# RF_DAC.net
KiCad netlist of a schematic drawn in Altium Designer
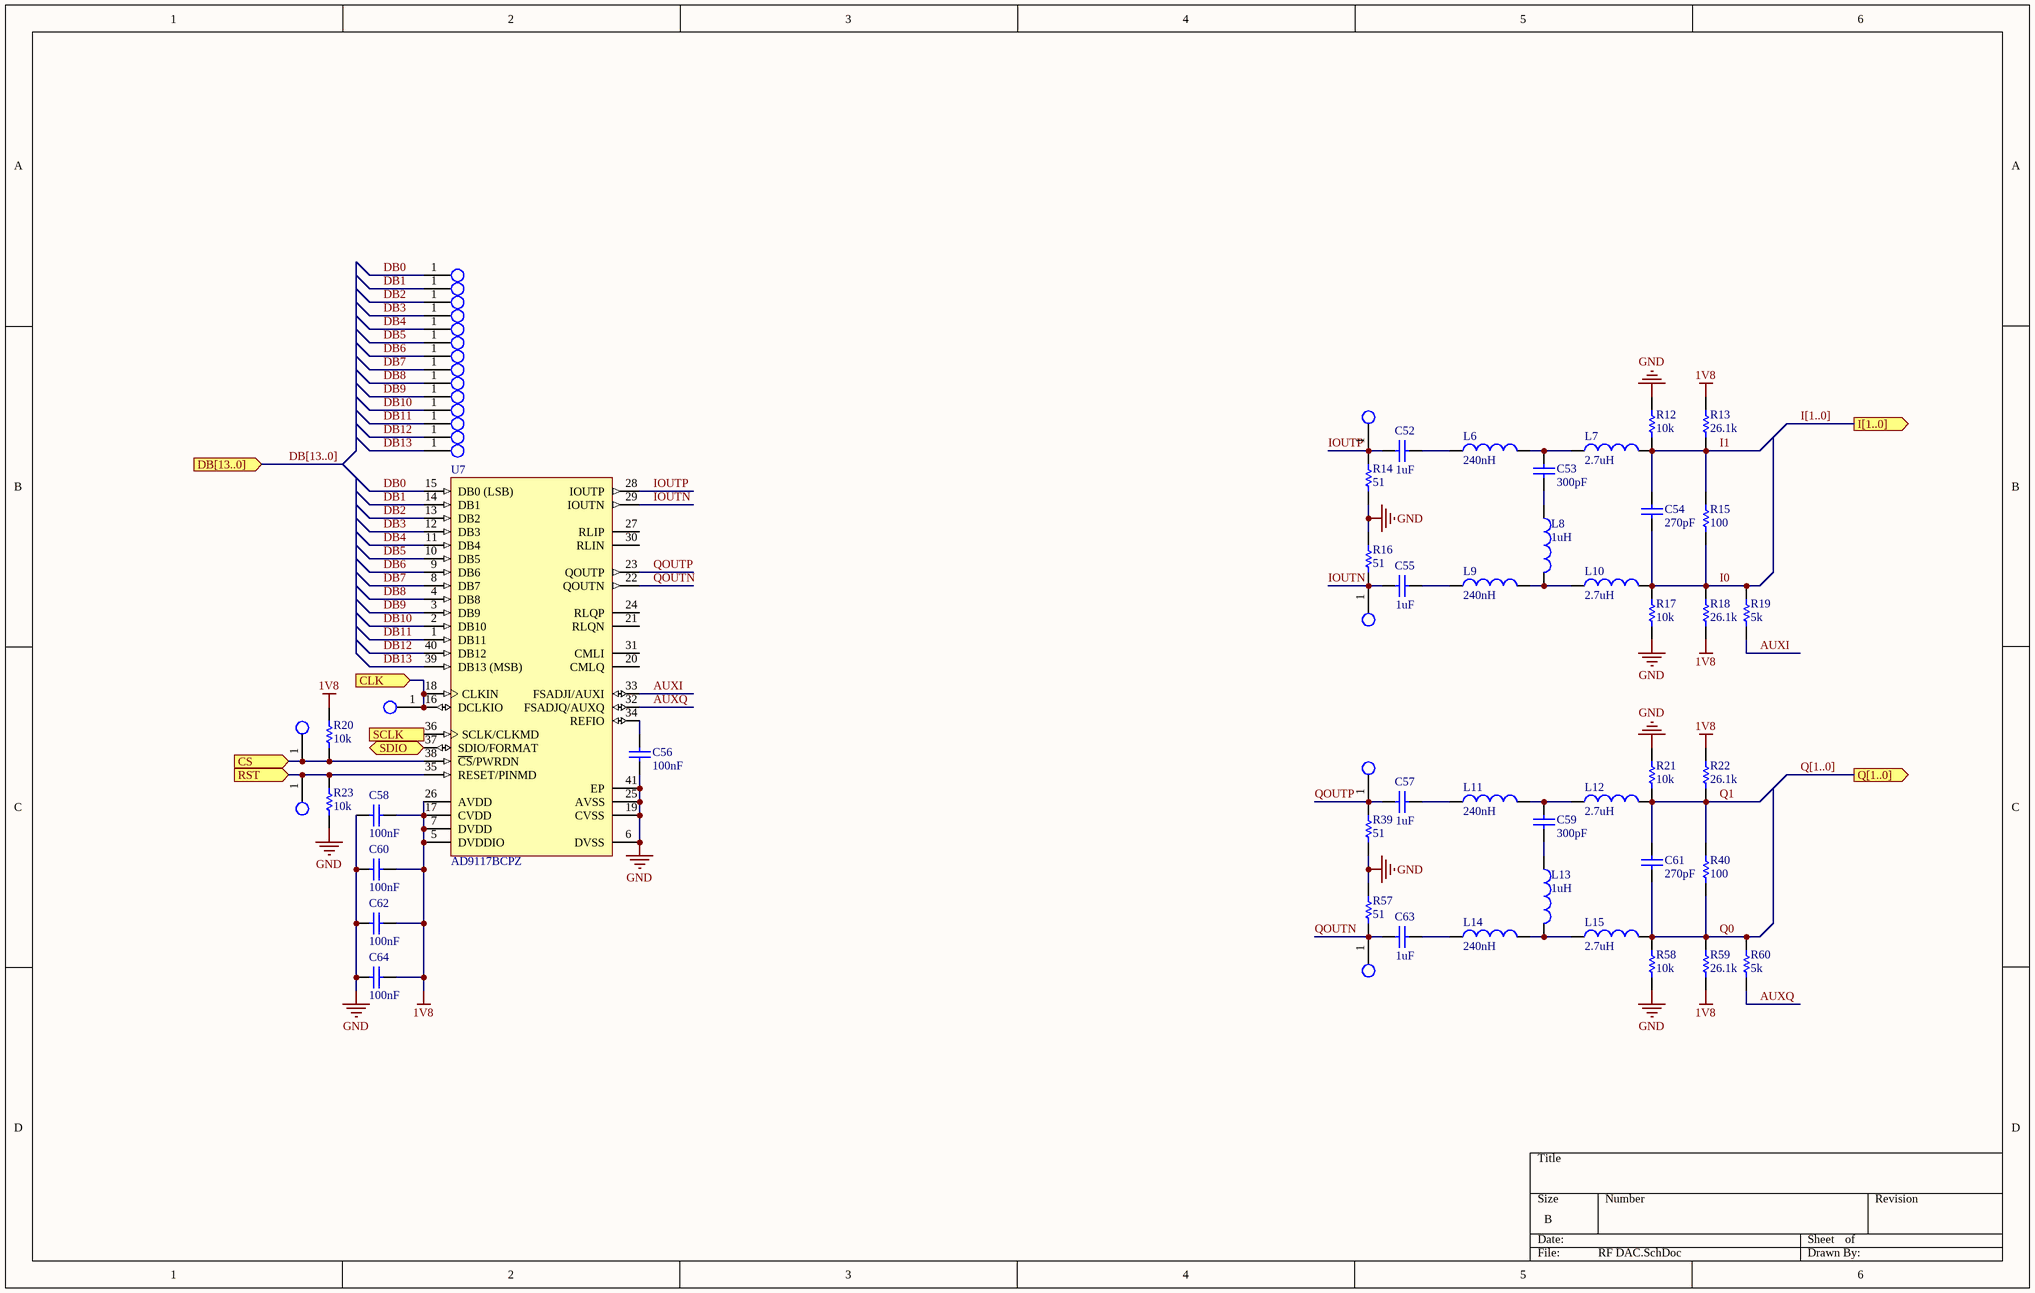
[diagram p0: RF DAC.SchDoc]

(export (version "E")
  (design (tool "Eeschema 10.0.6"))
  (components
    (comp (ref "C52")
      (value "1uF")
      (footprint "1608[0603]")
      (description "Capacitor")
      (fields (field (name "Comment") "Cap") (field (name "PUBLISHER") "Altium Limited"))
      (libsource (lib "Miscellaneous Devices") (part "Cap"))
    )
    (comp (ref "C53")
      (value "300pF")
      (footprint "0402-A")
      (description "Capacitor")
      (fields (field (name "Comment") "Cap") (field (name "PUBLISHER") "Altium Limited"))
      (libsource (lib "Miscellaneous Devices") (part "Cap"))
    )
    (comp (ref "C54")
      (value "270pF")
      (footprint "0402-A")
      (description "Capacitor")
      (fields (field (name "Comment") "Cap") (field (name "PUBLISHER") "Altium Limited"))
      (libsource (lib "Miscellaneous Devices") (part "Cap"))
    )
    (comp (ref "C55")
      (value "1uF")
      (footprint "1608[0603]")
      (description "Capacitor")
      (fields (field (name "Comment") "Cap") (field (name "PUBLISHER") "Altium Limited"))
      (libsource (lib "Miscellaneous Devices") (part "Cap"))
    )
    (comp (ref "C56")
      (value "100nF")
      (footprint "0402-A")
      (description "Capacitor")
      (fields (field (name "Comment") "Cap") (field (name "PUBLISHER") "Altium Limited"))
      (libsource (lib "Miscellaneous Devices") (part "Cap"))
    )
    (comp (ref "C57")
      (value "1uF")
      (footprint "1608[0603]")
      (description "Capacitor")
      (fields (field (name "Comment") "Cap") (field (name "PUBLISHER") "Altium Limited"))
      (libsource (lib "Miscellaneous Devices") (part "Cap"))
    )
    (comp (ref "C58")
      (value "100nF")
      (footprint "0402-A")
      (description "Capacitor")
      (fields (field (name "Comment") "Cap") (field (name "PUBLISHER") "Altium Limited"))
      (libsource (lib "Miscellaneous Devices") (part "Cap"))
    )
    (comp (ref "C59")
      (value "300pF")
      (footprint "0402-A")
      (description "Capacitor")
      (fields (field (name "Comment") "Cap") (field (name "PUBLISHER") "Altium Limited"))
      (libsource (lib "Miscellaneous Devices") (part "Cap"))
    )
    (comp (ref "C60")
      (value "100nF")
      (footprint "0402-A")
      (description "Capacitor")
      (fields (field (name "Comment") "Cap") (field (name "PUBLISHER") "Altium Limited"))
      (libsource (lib "Miscellaneous Devices") (part "Cap"))
    )
    (comp (ref "C61")
      (value "270pF")
      (footprint "0402-A")
      (description "Capacitor")
      (fields (field (name "Comment") "Cap") (field (name "PUBLISHER") "Altium Limited"))
      (libsource (lib "Miscellaneous Devices") (part "Cap"))
    )
    (comp (ref "C62")
      (value "100nF")
      (footprint "0402-A")
      (description "Capacitor")
      (fields (field (name "Comment") "Cap") (field (name "PUBLISHER") "Altium Limited"))
      (libsource (lib "Miscellaneous Devices") (part "Cap"))
    )
    (comp (ref "C63")
      (value "1uF")
      (footprint "1608[0603]")
      (description "Capacitor")
      (fields (field (name "Comment") "Cap") (field (name "PUBLISHER") "Altium Limited"))
      (libsource (lib "Miscellaneous Devices") (part "Cap"))
    )
    (comp (ref "C64")
      (value "100nF")
      (footprint "0402-A")
      (description "Capacitor")
      (fields (field (name "Comment") "Cap") (field (name "PUBLISHER") "Altium Limited"))
      (libsource (lib "Miscellaneous Devices") (part "Cap"))
    )
    (comp (ref "CLK")
      (value "5029")
      (footprint "EXPOSED PAD 0.02X0.02")
      (libsource (lib "5029") (part "5029"))
    )
    (comp (ref "CLK3")
      (value "5029")
      (footprint "EXPOSED PAD 0.02X0.02")
      (libsource (lib "5029") (part "5029"))
    )
    (comp (ref "CLK4")
      (value "5029")
      (footprint "EXPOSED PAD 0.02X0.02")
      (libsource (lib "5029") (part "5029"))
    )
    (comp (ref "DB0")
      (value "5029")
      (footprint "EXPOSED PAD 0.02X0.02")
      (libsource (lib "5029") (part "5029"))
    )
    (comp (ref "DB1")
      (value "5029")
      (footprint "EXPOSED PAD 0.02X0.02")
      (libsource (lib "5029") (part "5029"))
    )
    (comp (ref "DB2")
      (value "5029")
      (footprint "EXPOSED PAD 0.02X0.02")
      (libsource (lib "5029") (part "5029"))
    )
    (comp (ref "DB3")
      (value "5029")
      (footprint "EXPOSED PAD 0.02X0.02")
      (libsource (lib "5029") (part "5029"))
    )
    (comp (ref "DB4")
      (value "5029")
      (footprint "EXPOSED PAD 0.02X0.02")
      (libsource (lib "5029") (part "5029"))
    )
    (comp (ref "DB5")
      (value "5029")
      (footprint "EXPOSED PAD 0.02X0.02")
      (libsource (lib "5029") (part "5029"))
    )
    (comp (ref "DB6")
      (value "5029")
      (footprint "EXPOSED PAD 0.02X0.02")
      (libsource (lib "5029") (part "5029"))
    )
    (comp (ref "DB7")
      (value "5029")
      (footprint "EXPOSED PAD 0.02X0.02")
      (libsource (lib "5029") (part "5029"))
    )
    (comp (ref "DB8")
      (value "5029")
      (footprint "EXPOSED PAD 0.02X0.02")
      (libsource (lib "5029") (part "5029"))
    )
    (comp (ref "DB9")
      (value "5029")
      (footprint "EXPOSED PAD 0.02X0.02")
      (libsource (lib "5029") (part "5029"))
    )
    (comp (ref "DB10")
      (value "5029")
      (footprint "EXPOSED PAD 0.02X0.02")
      (libsource (lib "5029") (part "5029"))
    )
    (comp (ref "DB11")
      (value "5029")
      (footprint "EXPOSED PAD 0.02X0.02")
      (libsource (lib "5029") (part "5029"))
    )
    (comp (ref "DB12")
      (value "5029")
      (footprint "EXPOSED PAD 0.02X0.02")
      (libsource (lib "5029") (part "5029"))
    )
    (comp (ref "DB13")
      (value "5029")
      (footprint "EXPOSED PAD 0.02X0.02")
      (libsource (lib "5029") (part "5029"))
    )
    (comp (ref "J22")
      (value "5029")
      (footprint "EXPOSED PAD 0.02X0.02")
      (libsource (lib "5029") (part "5029"))
    )
    (comp (ref "J25")
      (value "5029")
      (footprint "EXPOSED PAD 0.02X0.02")
      (libsource (lib "5029") (part "5029"))
    )
    (comp (ref "J26")
      (value "5029")
      (footprint "EXPOSED PAD 0.02X0.02")
      (libsource (lib "5029") (part "5029"))
    )
    (comp (ref "J29")
      (value "5029")
      (footprint "EXPOSED PAD 0.02X0.02")
      (libsource (lib "5029") (part "5029"))
    )
    (comp (ref "L6")
      (value "240nH")
      (footprint "0402-A")
      (description "Inductor")
      (fields (field (name "PUBLISHER") "Altium Limited"))
      (libsource (lib "Miscellaneous Devices") (part "Inductor"))
    )
    (comp (ref "L7")
      (value "2.7uH")
      (footprint "1608[0603]")
      (description "Inductor")
      (fields (field (name "PUBLISHER") "Altium Limited"))
      (libsource (lib "Miscellaneous Devices") (part "Inductor"))
    )
    (comp (ref "L8")
      (value "1uH")
      (footprint "1608[0603]")
      (description "Inductor")
      (fields (field (name "PUBLISHER") "Altium Limited"))
      (libsource (lib "Miscellaneous Devices") (part "Inductor"))
    )
    (comp (ref "L9")
      (value "240nH")
      (footprint "0402-A")
      (description "Inductor")
      (fields (field (name "PUBLISHER") "Altium Limited"))
      (libsource (lib "Miscellaneous Devices") (part "Inductor"))
    )
    (comp (ref "L10")
      (value "2.7uH")
      (footprint "1608[0603]")
      (description "Inductor")
      (fields (field (name "PUBLISHER") "Altium Limited"))
      (libsource (lib "Miscellaneous Devices") (part "Inductor"))
    )
    (comp (ref "L11")
      (value "240nH")
      (footprint "0402-A")
      (description "Inductor")
      (fields (field (name "PUBLISHER") "Altium Limited"))
      (libsource (lib "Miscellaneous Devices") (part "Inductor"))
    )
    (comp (ref "L12")
      (value "2.7uH")
      (footprint "1608[0603]")
      (description "Inductor")
      (fields (field (name "PUBLISHER") "Altium Limited"))
      (libsource (lib "Miscellaneous Devices") (part "Inductor"))
    )
    (comp (ref "L13")
      (value "1uH")
      (footprint "1608[0603]")
      (description "Inductor")
      (fields (field (name "PUBLISHER") "Altium Limited"))
      (libsource (lib "Miscellaneous Devices") (part "Inductor"))
    )
    (comp (ref "L14")
      (value "240nH")
      (footprint "0402-A")
      (description "Inductor")
      (fields (field (name "PUBLISHER") "Altium Limited"))
      (libsource (lib "Miscellaneous Devices") (part "Inductor"))
    )
    (comp (ref "L15")
      (value "2.7uH")
      (footprint "1608[0603]")
      (description "Inductor")
      (fields (field (name "PUBLISHER") "Altium Limited"))
      (libsource (lib "Miscellaneous Devices") (part "Inductor"))
    )
    (comp (ref "R12")
      (value "10k")
      (footprint "0402-A")
      (description "Resistor")
      (fields (field (name "Comment") "Res1") (field (name "PUBLISHER") "Altium Limited"))
      (libsource (lib "Miscellaneous Devices") (part "Res1"))
    )
    (comp (ref "R13")
      (value "26.1k")
      (footprint "0402-A")
      (description "Resistor")
      (fields (field (name "Comment") "Res1") (field (name "PUBLISHER") "Altium Limited"))
      (libsource (lib "Miscellaneous Devices") (part "Res1"))
    )
    (comp (ref "R14")
      (value "51")
      (footprint "0402-A")
      (description "Resistor")
      (fields (field (name "Comment") "Res1") (field (name "PUBLISHER") "Altium Limited"))
      (libsource (lib "Miscellaneous Devices") (part "Res1"))
    )
    (comp (ref "R15")
      (value "100")
      (footprint "0402-A")
      (description "Resistor")
      (fields (field (name "Comment") "Res1") (field (name "PUBLISHER") "Altium Limited"))
      (libsource (lib "Miscellaneous Devices") (part "Res1"))
    )
    (comp (ref "R16")
      (value "51")
      (footprint "0402-A")
      (description "Resistor")
      (fields (field (name "Comment") "Res1") (field (name "PUBLISHER") "Altium Limited"))
      (libsource (lib "Miscellaneous Devices") (part "Res1"))
    )
    (comp (ref "R17")
      (value "10k")
      (footprint "0402-A")
      (description "Resistor")
      (fields (field (name "Comment") "Res1") (field (name "PUBLISHER") "Altium Limited"))
      (libsource (lib "Miscellaneous Devices") (part "Res1"))
    )
    (comp (ref "R18")
      (value "26.1k")
      (footprint "0402-A")
      (description "Resistor")
      (fields (field (name "Comment") "Res1") (field (name "PUBLISHER") "Altium Limited"))
      (libsource (lib "Miscellaneous Devices") (part "Res1"))
    )
    (comp (ref "R19")
      (value "5k")
      (footprint "0402-A")
      (description "Resistor")
      (fields (field (name "Comment") "Res1") (field (name "PUBLISHER") "Altium Limited"))
      (libsource (lib "Miscellaneous Devices") (part "Res1"))
    )
    (comp (ref "R20")
      (value "10k")
      (footprint "0402-A")
      (description "Resistor")
      (fields (field (name "Comment") "Res1") (field (name "PUBLISHER") "Altium Limited"))
      (libsource (lib "Miscellaneous Devices") (part "Res1"))
    )
    (comp (ref "R21")
      (value "10k")
      (footprint "0402-A")
      (description "Resistor")
      (fields (field (name "Comment") "Res1") (field (name "PUBLISHER") "Altium Limited"))
      (libsource (lib "Miscellaneous Devices") (part "Res1"))
    )
    (comp (ref "R22")
      (value "26.1k")
      (footprint "0402-A")
      (description "Resistor")
      (fields (field (name "Comment") "Res1") (field (name "PUBLISHER") "Altium Limited"))
      (libsource (lib "Miscellaneous Devices") (part "Res1"))
    )
    (comp (ref "R23")
      (value "10k")
      (footprint "0402-A")
      (description "Resistor")
      (fields (field (name "Comment") "Res1") (field (name "PUBLISHER") "Altium Limited"))
      (libsource (lib "Miscellaneous Devices") (part "Res1"))
    )
    (comp (ref "R39")
      (value "51")
      (footprint "0402-A")
      (description "Resistor")
      (fields (field (name "Comment") "Res1") (field (name "PUBLISHER") "Altium Limited"))
      (libsource (lib "Miscellaneous Devices") (part "Res1"))
    )
    (comp (ref "R40")
      (value "100")
      (footprint "0402-A")
      (description "Resistor")
      (fields (field (name "Comment") "Res1") (field (name "PUBLISHER") "Altium Limited"))
      (libsource (lib "Miscellaneous Devices") (part "Res1"))
    )
    (comp (ref "R57")
      (value "51")
      (footprint "0402-A")
      (description "Resistor")
      (fields (field (name "Comment") "Res1") (field (name "PUBLISHER") "Altium Limited"))
      (libsource (lib "Miscellaneous Devices") (part "Res1"))
    )
    (comp (ref "R58")
      (value "10k")
      (footprint "0402-A")
      (description "Resistor")
      (fields (field (name "Comment") "Res1") (field (name "PUBLISHER") "Altium Limited"))
      (libsource (lib "Miscellaneous Devices") (part "Res1"))
    )
    (comp (ref "R59")
      (value "26.1k")
      (footprint "0402-A")
      (description "Resistor")
      (fields (field (name "Comment") "Res1") (field (name "PUBLISHER") "Altium Limited"))
      (libsource (lib "Miscellaneous Devices") (part "Res1"))
    )
    (comp (ref "R60")
      (value "5k")
      (footprint "0402-A")
      (description "Resistor")
      (fields (field (name "Comment") "Res1") (field (name "PUBLISHER") "Altium Limited"))
      (libsource (lib "Miscellaneous Devices") (part "Res1"))
    )
    (comp (ref "U7")
      (value "AD9117BCPZ")
      (footprint "CP-40-1_N")
      (description "Dual 14-Bit Low Power TxDAC Digital-to-Analog Converter, 0 to +70 degC, CP-40-1, Pb-Free, Tray")
      (fields (field (name "MANUFACTURER") "Analog Devices") (field (name "GENERIC PART NUMBER") "AD9117"))
      (libsource (lib "Altium Content Vault") (part "ADI-AD9117-CP-40-1"))
    )
  )
  (nets
    (net (code "1") (name "/AUXI") (class "Default")
      (node (ref "R19") (pin "1") (pinfunction "1_1") (pintype "passive"))
      (node (ref "U7") (pin "33") (pinfunction "FSADJI/AUXI_33") (pintype "bidirectional"))
    )
    (net (code "2") (name "/AUXQ") (class "Default")
      (node (ref "R60") (pin "1") (pinfunction "1_1") (pintype "passive"))
      (node (ref "U7") (pin "32") (pinfunction "FSADJQ/AUXQ_32") (pintype "bidirectional"))
    )
    (net (code "3") (name "/CLK") (class "Default")
      (node (ref "CLK") (pin "1") (pintype "passive"))
      (node (ref "U7") (pin "16") (pinfunction "DCLKIO_16") (pintype "bidirectional"))
      (node (ref "U7") (pin "18") (pinfunction "CLKIN_18") (pintype "input"))
    )
    (net (code "4") (name "/CS") (class "Default")
      (node (ref "CLK3") (pin "1") (pintype "passive"))
      (node (ref "R20") (pin "1") (pinfunction "1_1") (pintype "passive"))
      (node (ref "U7") (pin "38") (pinfunction "~{CS}/PWRDN_38") (pintype "input"))
    )
    (net (code "5") (name "/DB0") (class "Default")
      (node (ref "DB0") (pin "1") (pintype "passive"))
      (node (ref "U7") (pin "15") (pinfunction "DB0_(LSB)_15") (pintype "input"))
    )
    (net (code "6") (name "/DB1") (class "Default")
      (node (ref "DB1") (pin "1") (pintype "passive"))
      (node (ref "U7") (pin "14") (pinfunction "DB1_14") (pintype "input"))
    )
    (net (code "7") (name "/DB2") (class "Default")
      (node (ref "DB2") (pin "1") (pintype "passive"))
      (node (ref "U7") (pin "13") (pinfunction "DB2_13") (pintype "input"))
    )
    (net (code "8") (name "/DB3") (class "Default")
      (node (ref "DB3") (pin "1") (pintype "passive"))
      (node (ref "U7") (pin "12") (pinfunction "DB3_12") (pintype "input"))
    )
    (net (code "9") (name "/DB4") (class "Default")
      (node (ref "DB4") (pin "1") (pintype "passive"))
      (node (ref "U7") (pin "11") (pinfunction "DB4_11") (pintype "input"))
    )
    (net (code "10") (name "/DB5") (class "Default")
      (node (ref "DB5") (pin "1") (pintype "passive"))
      (node (ref "U7") (pin "10") (pinfunction "DB5_10") (pintype "input"))
    )
    (net (code "11") (name "/DB6") (class "Default")
      (node (ref "DB6") (pin "1") (pintype "passive"))
      (node (ref "U7") (pin "9") (pinfunction "DB6_9") (pintype "input"))
    )
    (net (code "12") (name "/DB7") (class "Default")
      (node (ref "DB7") (pin "1") (pintype "passive"))
      (node (ref "U7") (pin "8") (pinfunction "DB7_8") (pintype "input"))
    )
    (net (code "13") (name "/DB8") (class "Default")
      (node (ref "DB8") (pin "1") (pintype "passive"))
      (node (ref "U7") (pin "4") (pinfunction "DB8_4") (pintype "input"))
    )
    (net (code "14") (name "/DB9") (class "Default")
      (node (ref "DB9") (pin "1") (pintype "passive"))
      (node (ref "U7") (pin "3") (pinfunction "DB9_3") (pintype "input"))
    )
    (net (code "15") (name "/DB10") (class "Default")
      (node (ref "DB10") (pin "1") (pintype "passive"))
      (node (ref "U7") (pin "2") (pinfunction "DB10_2") (pintype "input"))
    )
    (net (code "16") (name "/DB11") (class "Default")
      (node (ref "DB11") (pin "1") (pintype "passive"))
      (node (ref "U7") (pin "1") (pinfunction "DB11_1") (pintype "input"))
    )
    (net (code "17") (name "/DB12") (class "Default")
      (node (ref "DB12") (pin "1") (pintype "passive"))
      (node (ref "U7") (pin "40") (pinfunction "DB12_40") (pintype "input"))
    )
    (net (code "18") (name "/DB13") (class "Default")
      (node (ref "DB13") (pin "1") (pintype "passive"))
      (node (ref "U7") (pin "39") (pinfunction "DB13_(MSB)_39") (pintype "input"))
    )
    (net (code "20") (name "/I0") (class "Default")
      (node (ref "C54") (pin "2") (pinfunction "2_2") (pintype "passive"))
      (node (ref "L10") (pin "2") (pinfunction "2_2") (pintype "passive"))
      (node (ref "R15") (pin "1") (pinfunction "1_1") (pintype "passive"))
      (node (ref "R17") (pin "2") (pinfunction "2_2") (pintype "passive"))
      (node (ref "R18") (pin "2") (pinfunction "2_2") (pintype "passive"))
      (node (ref "R19") (pin "2") (pinfunction "2_2") (pintype "passive"))
    )
    (net (code "21") (name "/I1") (class "Default")
      (node (ref "C54") (pin "1") (pinfunction "1_1") (pintype "passive"))
      (node (ref "L7") (pin "2") (pinfunction "2_2") (pintype "passive"))
      (node (ref "R12") (pin "1") (pinfunction "1_1") (pintype "passive"))
      (node (ref "R13") (pin "1") (pinfunction "1_1") (pintype "passive"))
      (node (ref "R15") (pin "2") (pinfunction "2_2") (pintype "passive"))
    )
    (net (code "22") (name "/IOUTN") (class "Default")
      (node (ref "C55") (pin "2") (pinfunction "2_2") (pintype "passive"))
      (node (ref "J25") (pin "1") (pintype "passive"))
      (node (ref "R16") (pin "1") (pinfunction "1_1") (pintype "passive"))
      (node (ref "U7") (pin "29") (pinfunction "IOUTN_29") (pintype "output"))
    )
    (net (code "23") (name "/IOUTP") (class "Default")
      (node (ref "C52") (pin "2") (pinfunction "2_2") (pintype "passive"))
      (node (ref "J22") (pin "1") (pintype "passive"))
      (node (ref "R14") (pin "2") (pinfunction "2_2") (pintype "passive"))
      (node (ref "U7") (pin "28") (pinfunction "IOUTP_28") (pintype "output"))
    )
    (net (code "25") (name "/Q0") (class "Default")
      (node (ref "C61") (pin "2") (pinfunction "2_2") (pintype "passive"))
      (node (ref "L15") (pin "2") (pinfunction "2_2") (pintype "passive"))
      (node (ref "R40") (pin "1") (pinfunction "1_1") (pintype "passive"))
      (node (ref "R58") (pin "2") (pinfunction "2_2") (pintype "passive"))
      (node (ref "R59") (pin "2") (pinfunction "2_2") (pintype "passive"))
      (node (ref "R60") (pin "2") (pinfunction "2_2") (pintype "passive"))
    )
    (net (code "26") (name "/Q1") (class "Default")
      (node (ref "C61") (pin "1") (pinfunction "1_1") (pintype "passive"))
      (node (ref "L12") (pin "2") (pinfunction "2_2") (pintype "passive"))
      (node (ref "R21") (pin "1") (pinfunction "1_1") (pintype "passive"))
      (node (ref "R22") (pin "1") (pinfunction "1_1") (pintype "passive"))
      (node (ref "R40") (pin "2") (pinfunction "2_2") (pintype "passive"))
    )
    (net (code "27") (name "/QOUTN") (class "Default")
      (node (ref "C63") (pin "2") (pinfunction "2_2") (pintype "passive"))
      (node (ref "J29") (pin "1") (pintype "passive"))
      (node (ref "R57") (pin "1") (pinfunction "1_1") (pintype "passive"))
      (node (ref "U7") (pin "22") (pinfunction "QOUTN_22") (pintype "output"))
    )
    (net (code "28") (name "/QOUTP") (class "Default")
      (node (ref "C57") (pin "2") (pinfunction "2_2") (pintype "passive"))
      (node (ref "J26") (pin "1") (pintype "passive"))
      (node (ref "R39") (pin "2") (pinfunction "2_2") (pintype "passive"))
      (node (ref "U7") (pin "23") (pinfunction "QOUTP_23") (pintype "output"))
    )
    (net (code "30") (name "/RST") (class "Default")
      (node (ref "CLK4") (pin "1") (pintype "passive"))
      (node (ref "R23") (pin "2") (pinfunction "2_2") (pintype "passive"))
      (node (ref "U7") (pin "35") (pinfunction "RESET/PINMD_35") (pintype "input"))
    )
    (net (code "31") (name "/SCLK") (class "Default")
      (node (ref "U7") (pin "36") (pinfunction "SCLK/CLKMD_36") (pintype "input"))
    )
    (net (code "32") (name "/SDIO") (class "Default")
      (node (ref "U7") (pin "37") (pinfunction "SDIO/FORMAT_37") (pintype "bidirectional"))
    )
    (net (code "33") (name "1V8") (class "Default")
      (node (ref "C58") (pin "2") (pinfunction "2_2") (pintype "passive"))
      (node (ref "C60") (pin "2") (pinfunction "2_2") (pintype "passive"))
      (node (ref "C62") (pin "2") (pinfunction "2_2") (pintype "passive"))
      (node (ref "C64") (pin "2") (pinfunction "2_2") (pintype "passive"))
      (node (ref "R13") (pin "2") (pinfunction "2_2") (pintype "passive"))
      (node (ref "R18") (pin "1") (pinfunction "1_1") (pintype "passive"))
      (node (ref "R20") (pin "2") (pinfunction "2_2") (pintype "passive"))
      (node (ref "R22") (pin "2") (pinfunction "2_2") (pintype "passive"))
      (node (ref "R59") (pin "1") (pinfunction "1_1") (pintype "passive"))
      (node (ref "U7") (pin "17") (pinfunction "CVDD_17") (pintype "power_in"))
      (node (ref "U7") (pin "26") (pinfunction "AVDD_26") (pintype "power_in"))
      (node (ref "U7") (pin "5") (pinfunction "DVDDIO_5") (pintype "power_in"))
      (node (ref "U7") (pin "7") (pinfunction "DVDD_7") (pintype "power_in"))
    )
    (net (code "34") (name "GND") (class "Default")
      (node (ref "C56") (pin "1") (pinfunction "1_1") (pintype "passive"))
      (node (ref "C58") (pin "1") (pinfunction "1_1") (pintype "passive"))
      (node (ref "C60") (pin "1") (pinfunction "1_1") (pintype "passive"))
      (node (ref "C62") (pin "1") (pinfunction "1_1") (pintype "passive"))
      (node (ref "C64") (pin "1") (pinfunction "1_1") (pintype "passive"))
      (node (ref "R12") (pin "2") (pinfunction "2_2") (pintype "passive"))
      (node (ref "R14") (pin "1") (pinfunction "1_1") (pintype "passive"))
      (node (ref "R16") (pin "2") (pinfunction "2_2") (pintype "passive"))
      (node (ref "R17") (pin "1") (pinfunction "1_1") (pintype "passive"))
      (node (ref "R21") (pin "2") (pinfunction "2_2") (pintype "passive"))
      (node (ref "R23") (pin "1") (pinfunction "1_1") (pintype "passive"))
      (node (ref "R39") (pin "1") (pinfunction "1_1") (pintype "passive"))
      (node (ref "R57") (pin "2") (pinfunction "2_2") (pintype "passive"))
      (node (ref "R58") (pin "1") (pinfunction "1_1") (pintype "passive"))
      (node (ref "U7") (pin "19") (pinfunction "CVSS_19") (pintype "power_in"))
      (node (ref "U7") (pin "25") (pinfunction "AVSS_25") (pintype "power_in"))
      (node (ref "U7") (pin "41") (pinfunction "EP_41") (pintype "power_in"))
      (node (ref "U7") (pin "6") (pinfunction "DVSS_6") (pintype "power_in"))
    )
    (net (code "35") (name "Net-(C52-Pad1)") (class "Default")
      (node (ref "C52") (pin "1") (pinfunction "1_1") (pintype "passive"))
      (node (ref "L6") (pin "1") (pinfunction "1_1") (pintype "passive"))
    )
    (net (code "36") (name "Net-(C53-Pad1)") (class "Default")
      (node (ref "C53") (pin "1") (pinfunction "1_1") (pintype "passive"))
      (node (ref "L6") (pin "2") (pinfunction "2_2") (pintype "passive"))
      (node (ref "L7") (pin "1") (pinfunction "1_1") (pintype "passive"))
    )
    (net (code "37") (name "Net-(C53-Pad2)") (class "Default")
      (node (ref "C53") (pin "2") (pinfunction "2_2") (pintype "passive"))
      (node (ref "L8") (pin "1") (pinfunction "1_1") (pintype "passive"))
    )
    (net (code "38") (name "Net-(C55-Pad1)") (class "Default")
      (node (ref "C55") (pin "1") (pinfunction "1_1") (pintype "passive"))
      (node (ref "L9") (pin "1") (pinfunction "1_1") (pintype "passive"))
    )
    (net (code "39") (name "Net-(C57-Pad1)") (class "Default")
      (node (ref "C57") (pin "1") (pinfunction "1_1") (pintype "passive"))
      (node (ref "L11") (pin "1") (pinfunction "1_1") (pintype "passive"))
    )
    (net (code "40") (name "Net-(C59-Pad1)") (class "Default")
      (node (ref "C59") (pin "1") (pinfunction "1_1") (pintype "passive"))
      (node (ref "L11") (pin "2") (pinfunction "2_2") (pintype "passive"))
      (node (ref "L12") (pin "1") (pinfunction "1_1") (pintype "passive"))
    )
    (net (code "41") (name "Net-(C59-Pad2)") (class "Default")
      (node (ref "C59") (pin "2") (pinfunction "2_2") (pintype "passive"))
      (node (ref "L13") (pin "1") (pinfunction "1_1") (pintype "passive"))
    )
    (net (code "42") (name "Net-(C63-Pad1)") (class "Default")
      (node (ref "C63") (pin "1") (pinfunction "1_1") (pintype "passive"))
      (node (ref "L14") (pin "1") (pinfunction "1_1") (pintype "passive"))
    )
    (net (code "43") (name "Net-(L10-Pad1)") (class "Default")
      (node (ref "L10") (pin "1") (pinfunction "1_1") (pintype "passive"))
      (node (ref "L8") (pin "2") (pinfunction "2_2") (pintype "passive"))
      (node (ref "L9") (pin "2") (pinfunction "2_2") (pintype "passive"))
    )
    (net (code "44") (name "Net-(L13-Pad2)") (class "Default")
      (node (ref "L13") (pin "2") (pinfunction "2_2") (pintype "passive"))
      (node (ref "L14") (pin "2") (pinfunction "2_2") (pintype "passive"))
      (node (ref "L15") (pin "1") (pinfunction "1_1") (pintype "passive"))
    )
    (net (code "45") (name "Net-(U7-REFIO)") (class "Default")
      (node (ref "C56") (pin "2") (pinfunction "2_2") (pintype "passive"))
      (node (ref "U7") (pin "34") (pinfunction "REFIO_34") (pintype "bidirectional"))
    )
    (net (code "46") (name "unconnected-(U7-CMLI-Pad31)") (class "Default")
      (node (ref "U7") (pin "31") (pinfunction "CMLI_31") (pintype "passive"))
    )
    (net (code "47") (name "unconnected-(U7-CMLQ-Pad20)") (class "Default")
      (node (ref "U7") (pin "20") (pinfunction "CMLQ_20") (pintype "passive"))
    )
    (net (code "48") (name "unconnected-(U7-RLIN-Pad30)") (class "Default")
      (node (ref "U7") (pin "30") (pinfunction "RLIN_30") (pintype "passive"))
    )
    (net (code "49") (name "unconnected-(U7-RLIP-Pad27)") (class "Default")
      (node (ref "U7") (pin "27") (pinfunction "RLIP_27") (pintype "passive"))
    )
    (net (code "50") (name "unconnected-(U7-RLQN-Pad21)") (class "Default")
      (node (ref "U7") (pin "21") (pinfunction "RLQN_21") (pintype "passive"))
    )
    (net (code "51") (name "unconnected-(U7-RLQP-Pad24)") (class "Default")
      (node (ref "U7") (pin "24") (pinfunction "RLQP_24") (pintype "passive"))
    )
  )
)
